# 1_byte_input.net
KiCad netlist of a schematic drawn in EAGLE
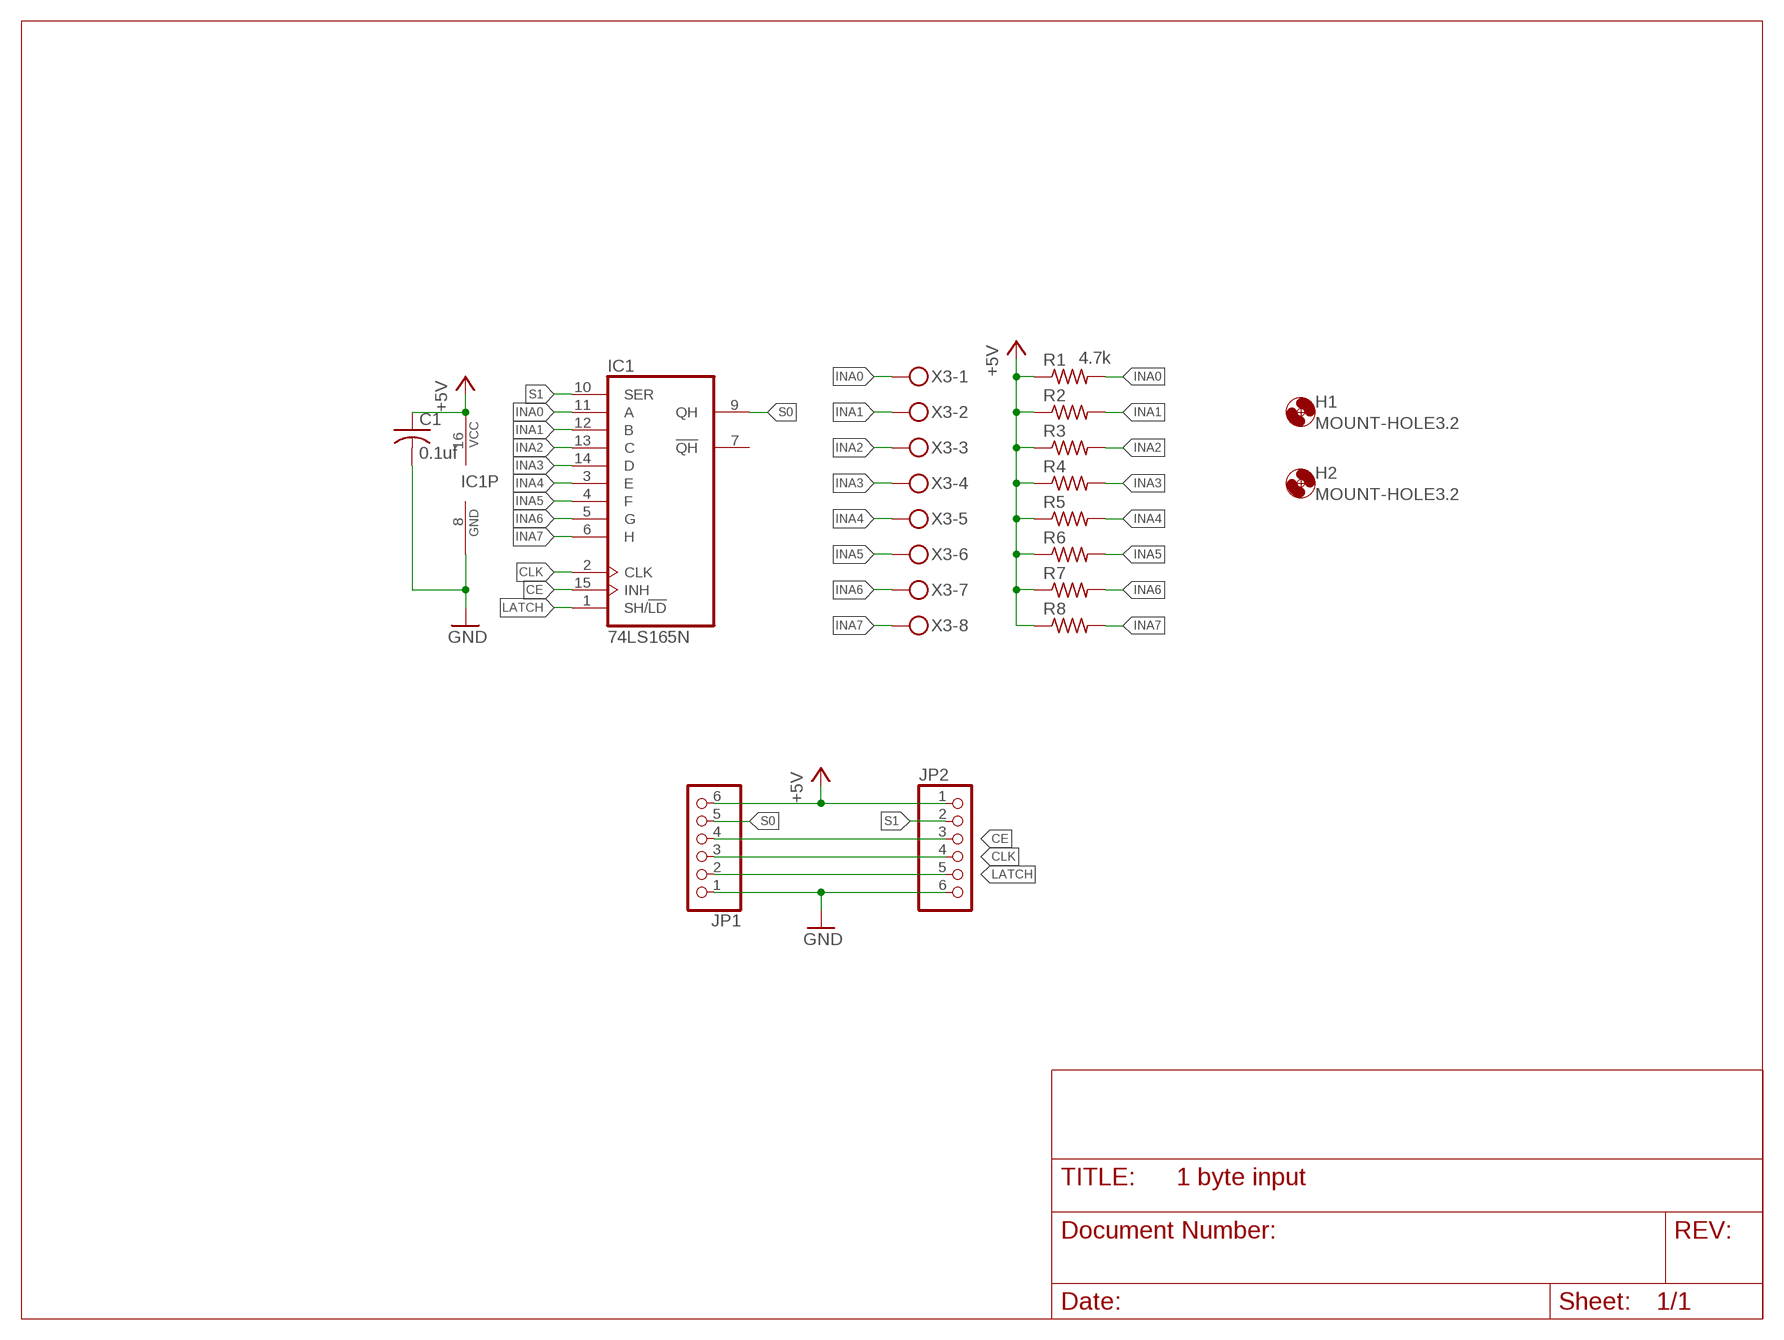
[diagram p0: schematic, sheet 1]

(export (version "E")
  (design (tool "Eeschema 10.0.6"))
  (components
    (comp (ref "C1")
      (value "0.1uf")
      (footprint "eagle-import:C025-025X050")
      (libsource (lib "eagle-import") (part "C-US025-025X050"))
    )
    (comp (ref "H1")
      (value "MOUNT-HOLE3.2")
      (footprint "eagle-import:3,2")
      (libsource (lib "eagle-import") (part "MOUNT-HOLE3.2"))
    )
    (comp (ref "H2")
      (value "MOUNT-HOLE3.2")
      (footprint "eagle-import:3,2")
      (libsource (lib "eagle-import") (part "MOUNT-HOLE3.2"))
    )
    (comp (ref "IC1")
      (value "74LS165N")
      (footprint "eagle-import:DIL16")
      (libsource (lib "eagle-import") (part "74165NLS"))
    )
    (comp (ref "JP1")
      (value "PINHD-1X6/90")
      (footprint "eagle-import:1X06_90")
      (libsource (lib "eagle-import") (part "PINHD-1X6/90"))
    )
    (comp (ref "JP2")
      (value "PINHD-1X6/90")
      (footprint "eagle-import:1X06_90")
      (libsource (lib "eagle-import") (part "PINHD-1X6/90"))
    )
    (comp (ref "R1")
      (value "4.7k")
      (footprint "eagle-import:0207_2V")
      (libsource (lib "eagle-import") (part "R-US_0207/2V"))
    )
    (comp (ref "R2")
      (value "R-US_0207/2V")
      (footprint "eagle-import:0207_2V")
      (libsource (lib "eagle-import") (part "R-US_0207/2V"))
    )
    (comp (ref "R3")
      (value "R-US_0207/2V")
      (footprint "eagle-import:0207_2V")
      (libsource (lib "eagle-import") (part "R-US_0207/2V"))
    )
    (comp (ref "R4")
      (value "R-US_0207/2V")
      (footprint "eagle-import:0207_2V")
      (libsource (lib "eagle-import") (part "R-US_0207/2V"))
    )
    (comp (ref "R5")
      (value "R-US_0207/2V")
      (footprint "eagle-import:0207_2V")
      (libsource (lib "eagle-import") (part "R-US_0207/2V"))
    )
    (comp (ref "R6")
      (value "R-US_0207/2V")
      (footprint "eagle-import:0207_2V")
      (libsource (lib "eagle-import") (part "R-US_0207/2V"))
    )
    (comp (ref "R7")
      (value "R-US_0207/2V")
      (footprint "eagle-import:0207_2V")
      (libsource (lib "eagle-import") (part "R-US_0207/2V"))
    )
    (comp (ref "R8")
      (value "R-US_0207/2V")
      (footprint "eagle-import:0207_2V")
      (libsource (lib "eagle-import") (part "R-US_0207/2V"))
    )
    (comp (ref "X3")
      (value "MKDSN1,5/8-5,08")
      (footprint "eagle-import:MKDSN1,5_8-5,08")
      (libsource (lib "eagle-import") (part "MKDSN1,5/8-5,08"))
    )
  )
  (nets
    (net (code "1") (name "+5V") (class "Default")
      (node (ref "C1") (pin "1") (pinfunction "1_1") (pintype "passive"))
      (node (ref "IC1") (pin "16") (pinfunction "VCC_16") (pintype "power_in"))
      (node (ref "JP1") (pin "6") (pinfunction "6_6") (pintype "passive"))
      (node (ref "JP2") (pin "1") (pinfunction "1_1") (pintype "passive"))
      (node (ref "R1") (pin "1") (pinfunction "1_1") (pintype "passive"))
      (node (ref "R2") (pin "1") (pinfunction "1_1") (pintype "passive"))
      (node (ref "R3") (pin "1") (pinfunction "1_1") (pintype "passive"))
      (node (ref "R4") (pin "1") (pinfunction "1_1") (pintype "passive"))
      (node (ref "R5") (pin "1") (pinfunction "1_1") (pintype "passive"))
      (node (ref "R6") (pin "1") (pinfunction "1_1") (pintype "passive"))
      (node (ref "R7") (pin "1") (pinfunction "1_1") (pintype "passive"))
      (node (ref "R8") (pin "1") (pinfunction "1_1") (pintype "passive"))
    )
    (net (code "2") (name "CE") (class "Default")
      (node (ref "IC1") (pin "15") (pinfunction "INH_15") (pintype "input"))
      (node (ref "JP1") (pin "4") (pinfunction "4_4") (pintype "passive"))
      (node (ref "JP2") (pin "3") (pinfunction "3_3") (pintype "passive"))
    )
    (net (code "3") (name "CLK") (class "Default")
      (node (ref "IC1") (pin "2") (pinfunction "CLK_2") (pintype "input"))
      (node (ref "JP1") (pin "3") (pinfunction "3_3") (pintype "passive"))
      (node (ref "JP2") (pin "4") (pinfunction "4_4") (pintype "passive"))
    )
    (net (code "4") (name "GND") (class "Default")
      (node (ref "C1") (pin "2") (pinfunction "2_2") (pintype "passive"))
      (node (ref "IC1") (pin "8") (pinfunction "GND_8") (pintype "power_in"))
      (node (ref "JP1") (pin "1") (pinfunction "1_1") (pintype "passive"))
      (node (ref "JP2") (pin "6") (pinfunction "6_6") (pintype "passive"))
    )
    (net (code "5") (name "INA0") (class "Default")
      (node (ref "IC1") (pin "11") (pinfunction "A_11") (pintype "input"))
      (node (ref "R1") (pin "2") (pinfunction "2_2") (pintype "passive"))
      (node (ref "X3") (pin "1") (pinfunction "KL_1") (pintype "passive"))
    )
    (net (code "6") (name "INA1") (class "Default")
      (node (ref "IC1") (pin "12") (pinfunction "B_12") (pintype "input"))
      (node (ref "R2") (pin "2") (pinfunction "2_2") (pintype "passive"))
      (node (ref "X3") (pin "2") (pinfunction "KL_2") (pintype "passive"))
    )
    (net (code "7") (name "INA2") (class "Default")
      (node (ref "IC1") (pin "13") (pinfunction "C_13") (pintype "input"))
      (node (ref "R3") (pin "2") (pinfunction "2_2") (pintype "passive"))
      (node (ref "X3") (pin "3") (pinfunction "KL_3") (pintype "passive"))
    )
    (net (code "8") (name "INA3") (class "Default")
      (node (ref "IC1") (pin "14") (pinfunction "D_14") (pintype "input"))
      (node (ref "R4") (pin "2") (pinfunction "2_2") (pintype "passive"))
      (node (ref "X3") (pin "4") (pinfunction "KL_4") (pintype "passive"))
    )
    (net (code "9") (name "INA4") (class "Default")
      (node (ref "IC1") (pin "3") (pinfunction "E_3") (pintype "input"))
      (node (ref "R5") (pin "2") (pinfunction "2_2") (pintype "passive"))
      (node (ref "X3") (pin "5") (pinfunction "KL_5") (pintype "passive"))
    )
    (net (code "10") (name "INA5") (class "Default")
      (node (ref "IC1") (pin "4") (pinfunction "F_4") (pintype "input"))
      (node (ref "R6") (pin "2") (pinfunction "2_2") (pintype "passive"))
      (node (ref "X3") (pin "6") (pinfunction "KL_6") (pintype "passive"))
    )
    (net (code "11") (name "INA6") (class "Default")
      (node (ref "IC1") (pin "5") (pinfunction "G_5") (pintype "input"))
      (node (ref "R7") (pin "2") (pinfunction "2_2") (pintype "passive"))
      (node (ref "X3") (pin "7") (pinfunction "KL_7") (pintype "passive"))
    )
    (net (code "12") (name "INA7") (class "Default")
      (node (ref "IC1") (pin "6") (pinfunction "H_6") (pintype "input"))
      (node (ref "R8") (pin "2") (pinfunction "2_2") (pintype "passive"))
      (node (ref "X3") (pin "8") (pinfunction "KL_8") (pintype "passive"))
    )
    (net (code "13") (name "LATCH") (class "Default")
      (node (ref "IC1") (pin "1") (pinfunction "SH/~{LD}_1") (pintype "input"))
      (node (ref "JP1") (pin "2") (pinfunction "2_2") (pintype "passive"))
      (node (ref "JP2") (pin "5") (pinfunction "5_5") (pintype "passive"))
    )
    (net (code "14") (name "S0") (class "Default")
      (node (ref "IC1") (pin "9") (pinfunction "QH_9") (pintype "output"))
      (node (ref "JP1") (pin "5") (pinfunction "5_5") (pintype "passive"))
    )
    (net (code "15") (name "S1") (class "Default")
      (node (ref "IC1") (pin "10") (pinfunction "SER_10") (pintype "input"))
      (node (ref "JP2") (pin "2") (pinfunction "2_2") (pintype "passive"))
    )
    (net (code "16") (name "unconnected-(IC1A-~{QH}-Pad7)") (class "Default")
      (node (ref "IC1") (pin "7") (pinfunction "~{QH}_7") (pintype "output"))
    )
  )
)
